# Pedal_Board_Power_Supply.net
KiCad netlist of a schematic drawn in EAGLE
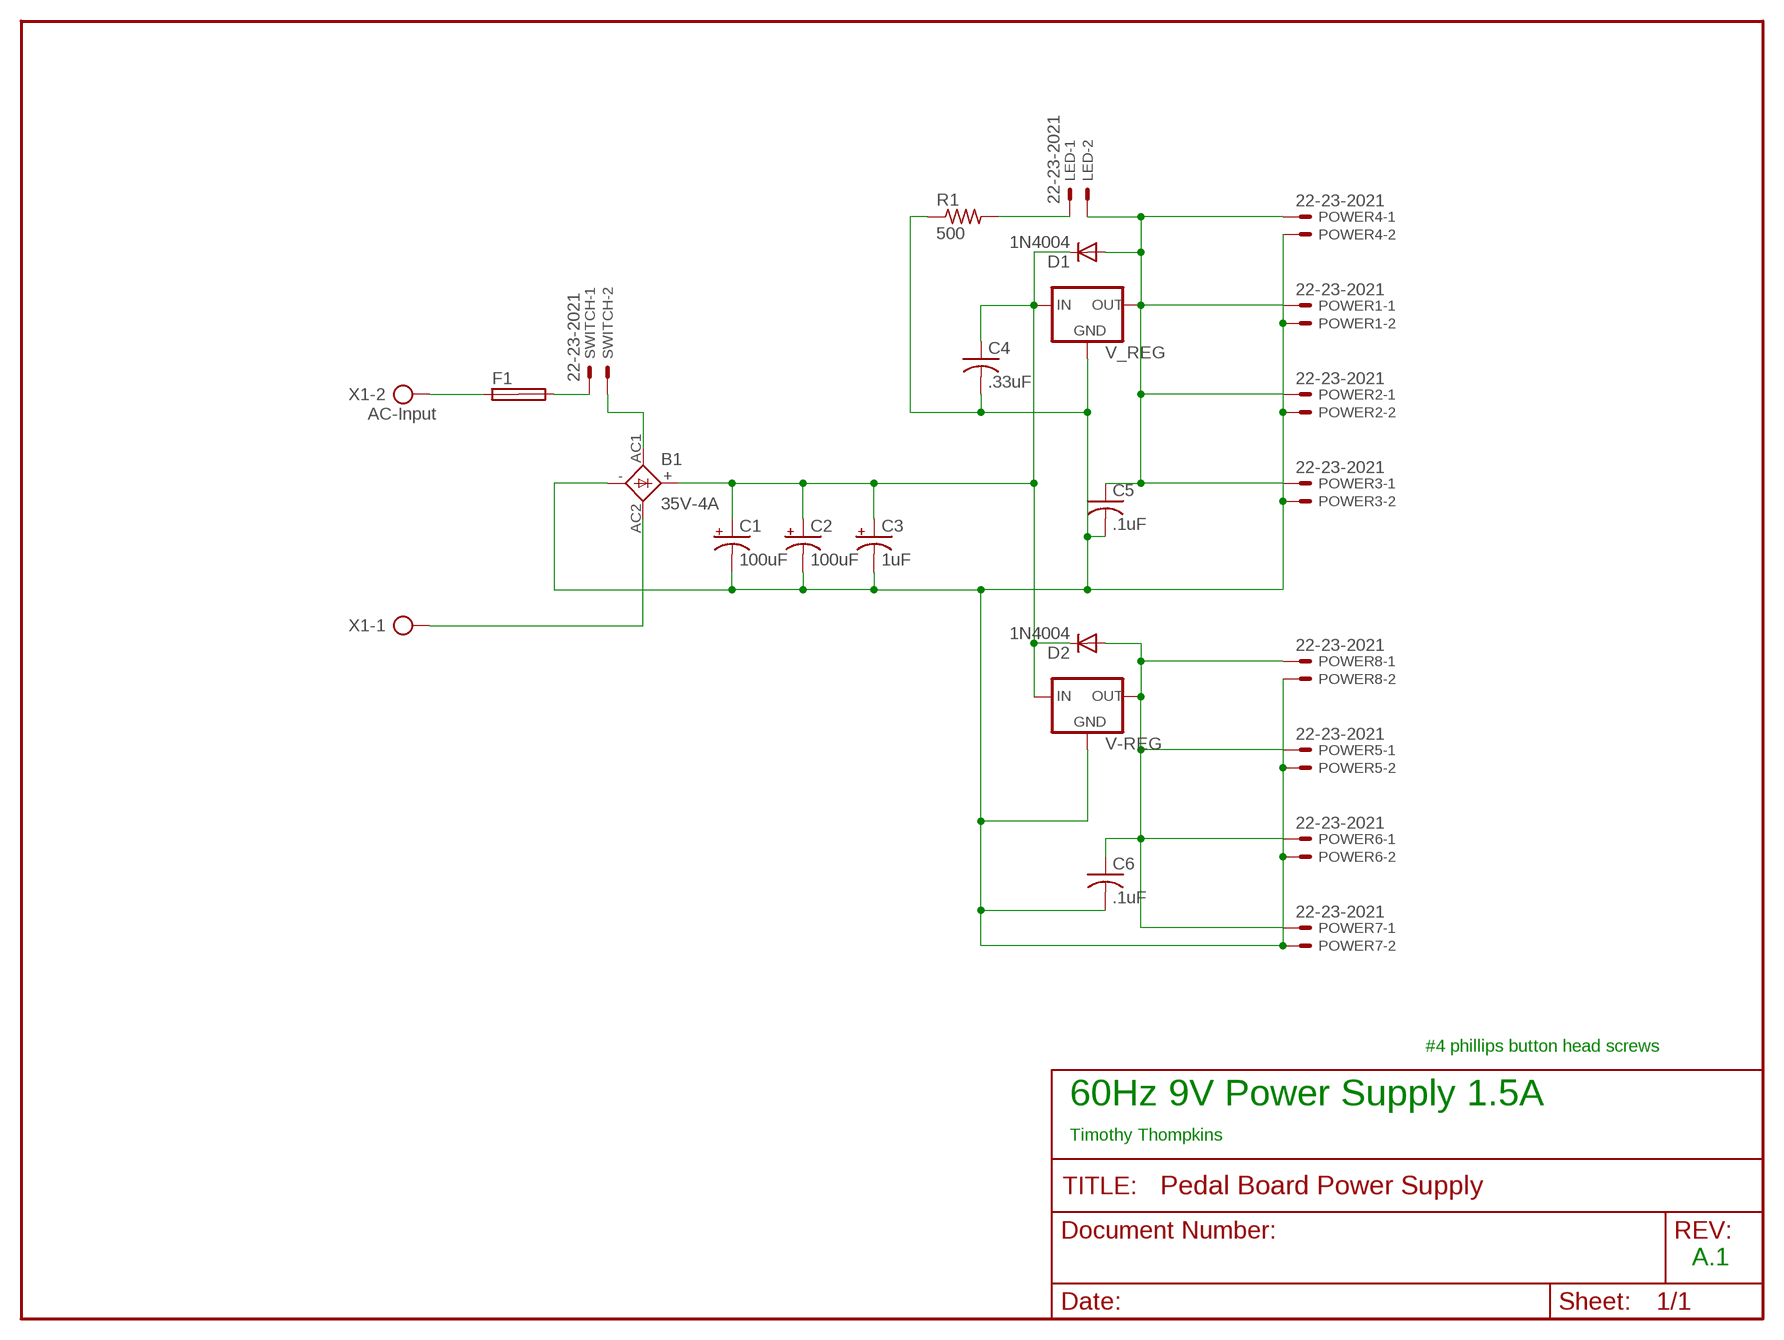
[diagram p0: schematic, sheet 1]

(export (version "E")
  (design (tool "Eeschema 10.0.6"))
  (components
    (comp (ref "B1")
      (value "35V-4A")
      (footprint "eagle-import:GBL")
      (libsource (lib "eagle-import") (part "GBL005"))
    )
    (comp (ref "C1")
      (value "100uF")
      (footprint "eagle-import:E3,5-10")
      (libsource (lib "eagle-import") (part "CPOL-USE3.5-10"))
    )
    (comp (ref "C2")
      (value "100uF")
      (footprint "eagle-import:E3,5-10")
      (libsource (lib "eagle-import") (part "CPOL-USE3.5-10"))
    )
    (comp (ref "C3")
      (value "1uF")
      (footprint "eagle-import:E3,5-10")
      (libsource (lib "eagle-import") (part "CPOL-USE3.5-10"))
    )
    (comp (ref "C4")
      (value ".33uF")
      (footprint "eagle-import:C050-025X075")
      (libsource (lib "eagle-import") (part "C-US050-025X075"))
    )
    (comp (ref "C5")
      (value ".1uF")
      (footprint "eagle-import:C050-025X075")
      (libsource (lib "eagle-import") (part "C-US050-025X075"))
    )
    (comp (ref "C6")
      (value ".1uF")
      (footprint "eagle-import:C050-025X075")
      (libsource (lib "eagle-import") (part "C-US050-025X075"))
    )
    (comp (ref "D1")
      (value "1N4004")
      (footprint "eagle-import:DO41-10")
      (libsource (lib "eagle-import") (part "1N4004"))
    )
    (comp (ref "D2")
      (value "1N4004")
      (footprint "eagle-import:DO41-10")
      (libsource (lib "eagle-import") (part "1N4004"))
    )
    (comp (ref "F1")
      (value "SHK20Q")
      (footprint "eagle-import:SHK20Q")
      (libsource (lib "eagle-import") (part "SHK20Q"))
    )
    (comp (ref "LED")
      (value "22-23-2021")
      (footprint "eagle-import:22-23-2021")
      (libsource (lib "eagle-import") (part "22-23-2021"))
    )
    (comp (ref "POWER1")
      (value "22-23-2021")
      (footprint "eagle-import:22-23-2021")
      (libsource (lib "eagle-import") (part "22-23-2021"))
    )
    (comp (ref "POWER2")
      (value "22-23-2021")
      (footprint "eagle-import:22-23-2021")
      (libsource (lib "eagle-import") (part "22-23-2021"))
    )
    (comp (ref "POWER3")
      (value "22-23-2021")
      (footprint "eagle-import:22-23-2021")
      (libsource (lib "eagle-import") (part "22-23-2021"))
    )
    (comp (ref "POWER4")
      (value "22-23-2021")
      (footprint "eagle-import:22-23-2021")
      (libsource (lib "eagle-import") (part "22-23-2021"))
    )
    (comp (ref "POWER5")
      (value "22-23-2021")
      (footprint "eagle-import:22-23-2021")
      (libsource (lib "eagle-import") (part "22-23-2021"))
    )
    (comp (ref "POWER6")
      (value "22-23-2021")
      (footprint "eagle-import:22-23-2021")
      (libsource (lib "eagle-import") (part "22-23-2021"))
    )
    (comp (ref "POWER7")
      (value "22-23-2021")
      (footprint "eagle-import:22-23-2021")
      (libsource (lib "eagle-import") (part "22-23-2021"))
    )
    (comp (ref "POWER8")
      (value "22-23-2021")
      (footprint "eagle-import:22-23-2021")
      (libsource (lib "eagle-import") (part "22-23-2021"))
    )
    (comp (ref "R1")
      (value "500")
      (footprint "eagle-import:0204_7")
      (libsource (lib "eagle-import") (part "R-US_0204/7"))
    )
    (comp (ref "SWITCH")
      (value "22-23-2021")
      (footprint "eagle-import:22-23-2021")
      (libsource (lib "eagle-import") (part "22-23-2021"))
    )
    (comp (ref "V-REG")
      (value "V_REG_78XXSINK")
      (footprint "eagle-import:TO220-IGO")
      (libsource (lib "eagle-import") (part "V_REG_78XXSINK"))
    )
    (comp (ref "V_REG")
      (value "V_REG_78XXSINK")
      (footprint "eagle-import:TO220-IGO")
      (libsource (lib "eagle-import") (part "V_REG_78XXSINK"))
    )
    (comp (ref "X1")
      (value "AC-Input")
      (footprint "eagle-import:AK500_2")
      (fields (field (name "OC_NEWARK") "unknown"))
      (libsource (lib "eagle-import") (part "AK500/2"))
    )
  )
  (nets
    (net (code "1") (name "Net-(B1-Pad+)") (class "Default")
      (node (ref "B1") (pin "+") (pinfunction "+_+") (pintype "passive"))
      (node (ref "C1") (pin "+") (pinfunction "+_+") (pintype "passive"))
      (node (ref "C2") (pin "+") (pinfunction "+_+") (pintype "passive"))
      (node (ref "C3") (pin "+") (pinfunction "+_+") (pintype "passive"))
      (node (ref "C4") (pin "1") (pinfunction "1_1") (pintype "passive"))
      (node (ref "D1") (pin "C") (pinfunction "C_C") (pintype "passive"))
      (node (ref "D2") (pin "C") (pinfunction "C_C") (pintype "passive"))
      (node (ref "V-REG") (pin "IN") (pinfunction "IN_IN") (pintype "input"))
      (node (ref "V_REG") (pin "IN") (pinfunction "IN_IN") (pintype "input"))
    )
    (net (code "2") (name "Net-(LEDA-S)") (class "Default")
      (node (ref "LED") (pin "1") (pinfunction "S_1") (pintype "passive"))
      (node (ref "R1") (pin "2") (pinfunction "2_2") (pintype "passive"))
    )
    (net (code "3") (name "Net-(LEDB-S)") (class "Default")
      (node (ref "C5") (pin "1") (pinfunction "1_1") (pintype "passive"))
      (node (ref "D1") (pin "A") (pinfunction "A_A") (pintype "passive"))
      (node (ref "LED") (pin "2") (pinfunction "S_2") (pintype "passive"))
      (node (ref "POWER1") (pin "1") (pinfunction "S_1") (pintype "passive"))
      (node (ref "POWER2") (pin "1") (pinfunction "S_1") (pintype "passive"))
      (node (ref "POWER3") (pin "1") (pinfunction "S_1") (pintype "passive"))
      (node (ref "POWER4") (pin "1") (pinfunction "S_1") (pintype "passive"))
      (node (ref "V_REG") (pin "OUT") (pinfunction "OUT_OUT") (pintype "output"))
    )
    (net (code "4") (name "Net-(POWER1B-S)") (class "Default")
      (node (ref "B1") (pin "-") (pinfunction "-_-") (pintype "passive"))
      (node (ref "C1") (pin "-") (pinfunction "-_-") (pintype "passive"))
      (node (ref "C2") (pin "-") (pinfunction "-_-") (pintype "passive"))
      (node (ref "C3") (pin "-") (pinfunction "-_-") (pintype "passive"))
      (node (ref "C4") (pin "2") (pinfunction "2_2") (pintype "passive"))
      (node (ref "C5") (pin "2") (pinfunction "2_2") (pintype "passive"))
      (node (ref "C6") (pin "2") (pinfunction "2_2") (pintype "passive"))
      (node (ref "POWER1") (pin "2") (pinfunction "S_2") (pintype "passive"))
      (node (ref "POWER2") (pin "2") (pinfunction "S_2") (pintype "passive"))
      (node (ref "POWER3") (pin "2") (pinfunction "S_2") (pintype "passive"))
      (node (ref "POWER4") (pin "2") (pinfunction "S_2") (pintype "passive"))
      (node (ref "POWER5") (pin "2") (pinfunction "S_2") (pintype "passive"))
      (node (ref "POWER6") (pin "2") (pinfunction "S_2") (pintype "passive"))
      (node (ref "POWER7") (pin "2") (pinfunction "S_2") (pintype "passive"))
      (node (ref "POWER8") (pin "2") (pinfunction "S_2") (pintype "passive"))
      (node (ref "R1") (pin "1") (pinfunction "1_1") (pintype "passive"))
      (node (ref "V-REG") (pin "GND") (pinfunction "GND_GND") (pintype "input"))
      (node (ref "V_REG") (pin "GND") (pinfunction "GND_GND") (pintype "input"))
    )
    (net (code "5") (name "Net-(POWER5A-S)") (class "Default")
      (node (ref "C6") (pin "1") (pinfunction "1_1") (pintype "passive"))
      (node (ref "D2") (pin "A") (pinfunction "A_A") (pintype "passive"))
      (node (ref "POWER5") (pin "1") (pinfunction "S_1") (pintype "passive"))
      (node (ref "POWER6") (pin "1") (pinfunction "S_1") (pintype "passive"))
      (node (ref "POWER7") (pin "1") (pinfunction "S_1") (pintype "passive"))
      (node (ref "POWER8") (pin "1") (pinfunction "S_1") (pintype "passive"))
      (node (ref "V-REG") (pin "OUT") (pinfunction "OUT_OUT") (pintype "output"))
    )
    (net (code "6") (name "Net-(SWITCHA-S)") (class "Default")
      (node (ref "F1") (pin "2A") (pinfunction "2A_2A") (pintype "passive"))
      (node (ref "SWITCH") (pin "1") (pinfunction "S_1") (pintype "passive"))
    )
    (net (code "7") (name "Net-(SWITCHB-S)") (class "Default")
      (node (ref "B1") (pin "AC1") (pinfunction "AC1_AC1") (pintype "passive"))
      (node (ref "SWITCH") (pin "2") (pinfunction "S_2") (pintype "passive"))
    )
    (net (code "8") (name "Net-(X1A-KL)") (class "Default")
      (node (ref "B1") (pin "AC2") (pinfunction "AC2_AC2") (pintype "passive"))
      (node (ref "X1") (pin "1") (pinfunction "KL_1") (pintype "passive"))
    )
    (net (code "9") (name "Net-(X1B-KL)") (class "Default")
      (node (ref "F1") (pin "1A") (pinfunction "1A_1A") (pintype "passive"))
      (node (ref "X1") (pin "2") (pinfunction "KL_2") (pintype "passive"))
    )
    (net (code "10") (name "unconnected-(F1-Pad1B)") (class "Default")
      (node (ref "F1") (pin "1B") (pinfunction "1B_1B") (pintype "passive"))
    )
    (net (code "11") (name "unconnected-(F1-Pad2B)") (class "Default")
      (node (ref "F1") (pin "2B") (pinfunction "2B_2B") (pintype "passive"))
    )
  )
)
